# PanQHDMI.net
KiCad netlist of a schematic drawn in Altium Designer
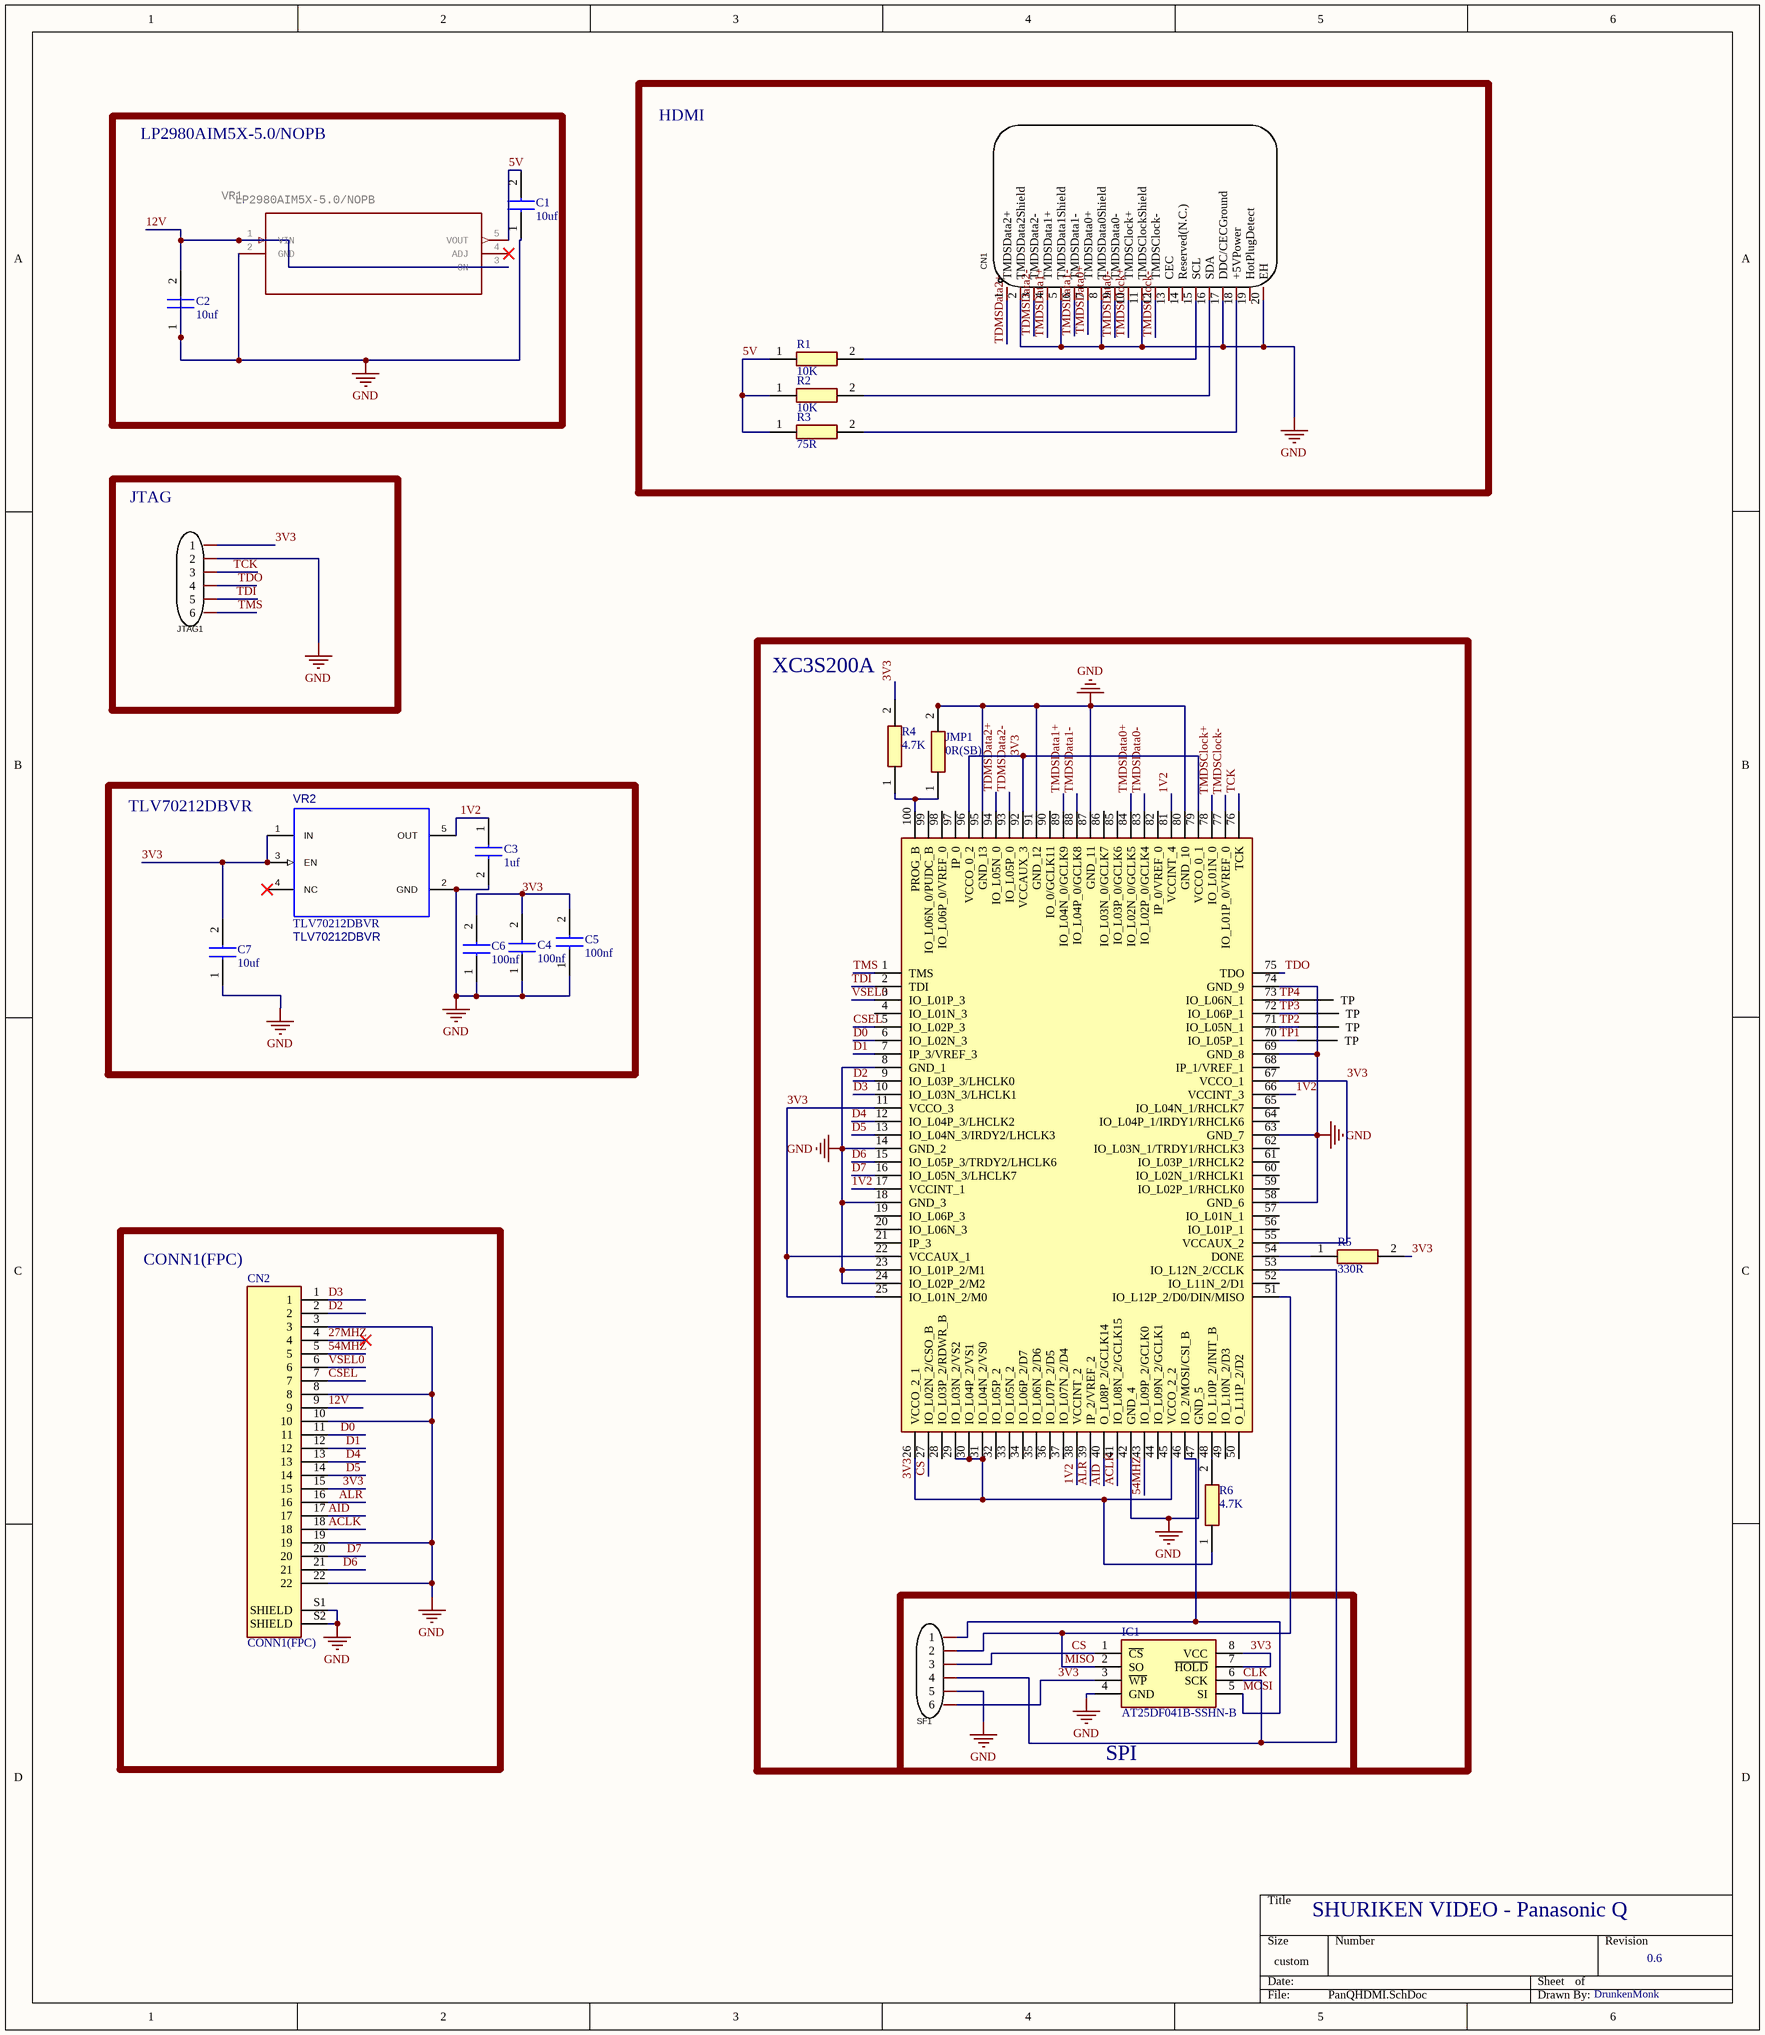
[diagram p0: PanQHDMI.SchDoc]

(export (version "E")
  (design (tool "Eeschema 10.0.6"))
  (components
    (comp (ref "C1")
      (value "10uf")
      (footprint "SamacSys:RESC2012X50N")
      (description "Capacitor")
      (fields
        (field (name "MANUFACTURER_PART_NUMBER") "08055A150JAT2A")
        (field (name "MOUSER PART NUMBER") "581-08055A150J")
      )
      (libsource (lib "*") (part "08055A150JAT2A"))
    )
    (comp (ref "C2")
      (value "10uf")
      (footprint "SamacSys:RESC2012X50N")
      (description "Capacitor")
      (fields
        (field (name "MANUFACTURER_PART_NUMBER") "08055A150JAT2A")
        (field (name "MOUSER PART NUMBER") "581-08055A150J")
      )
      (libsource (lib "*") (part "08055A150JAT2A"))
    )
    (comp (ref "C3")
      (value "1uf")
      (footprint "SamacSys:RESC2012X50N")
      (description "Capacitor")
      (fields
        (field (name "MANUFACTURER_PART_NUMBER") "08055A150JAT2A")
        (field (name "MOUSER PART NUMBER") "581-08055A150J")
      )
      (libsource (lib "*") (part "08055A150JAT2A"))
    )
    (comp (ref "C4")
      (value "100nf")
      (footprint "RESC2012X50N")
      (description "Capacitor")
      (fields
        (field (name "MANUFACTURER_PART_NUMBER") "08055A150JAT2A")
        (field (name "MOUSER PART NUMBER") "581-08055A150J")
      )
      (libsource (lib "*") (part "08055A150JAT2A"))
    )
    (comp (ref "C5")
      (value "100nf")
      (footprint "RESC2012X50N")
      (description "Capacitor")
      (fields
        (field (name "MANUFACTURER_PART_NUMBER") "08055A150JAT2A")
        (field (name "MOUSER PART NUMBER") "581-08055A150J")
      )
      (libsource (lib "*") (part "08055A150JAT2A"))
    )
    (comp (ref "C6")
      (value "100nf")
      (footprint "SamacSys:RESC2012X50N")
      (description "Capacitor")
      (fields
        (field (name "MANUFACTURER_PART_NUMBER") "08055A150JAT2A")
        (field (name "MOUSER PART NUMBER") "581-08055A150J")
      )
      (libsource (lib "*") (part "08055A150JAT2A"))
    )
    (comp (ref "C7")
      (value "10uf")
      (footprint "SamacSys:RESC2012X50N")
      (description "Capacitor")
      (fields
        (field (name "MANUFACTURER_PART_NUMBER") "08055A150JAT2A")
        (field (name "MOUSER PART NUMBER") "581-08055A150J")
      )
      (libsource (lib "*") (part "08055A150JAT2A"))
    )
    (comp (ref "CN1")
      (value "10029449-111RLF")
      (footprint "HDMI-SMD_10029449-001RLF")
      (fields (field (name "MANUFACTURER") "Amphenol"))
      (libsource (lib "altium-import") (part "root_1_10029449-111RLF_"))
    )
    (comp (ref "CN2")
      (value "CONN1(FPC)")
      (footprint "SamacSys:XF3M122151B")
      (description "Conn FPC Connector SKT 22 POS 1mm Solder RA SMD Automotive T/R")
      (fields (field (name "MP") "2-84953-2") (field (name "MF") "TE Connectivity / AMP"))
      (libsource (lib "2-84953-2") (part "2-84953-2"))
    )
    (comp (ref "IC1")
      (value "AT25DF041B-SSHN-B")
      (footprint "SamacSys:SOIC127P600X175-8N")
      (description "Integrated Circuit")
      (fields (field (name "MOUSER PART NUMBER") "988-AT25DF041BSSHNB"))
      (libsource (lib "*") (part "AT25DF041B-SSHN-B"))
    )
    (comp (ref "JMP1")
      (value "0R(SB)")
      (footprint "SamacSys:RESC2012X50N")
      (description "Resistor")
      (fields (field (name "MANUFACTURER_PART_NUMBER") "CPF0805B102RE1"))
      (libsource (lib "*") (part "CPF0805B102RE1"))
    )
    (comp (ref "JTAG1")
      (value "2.54-1x6P直针")
      (footprint "TC2030MCP")
      (fields (field (name "MANUFACTURER") "BOOMELE(博穆精密)"))
      (libsource (lib "altium-import") (part "root_0_mirrored_2.54-1x6P直针_"))
    )
    (comp (ref "R1")
      (value "10K")
      (footprint "SamacSys:RESC2012X50N")
      (description "Resistor")
      (fields (field (name "MANUFACTURER_PART_NUMBER") "CPF0805B102RE1"))
      (libsource (lib "") (part "CPF0805B102RE1_1"))
    )
    (comp (ref "R2")
      (value "10K")
      (footprint "SamacSys:RESC2012X50N")
      (description "Resistor")
      (fields (field (name "MANUFACTURER_PART_NUMBER") "CPF0805B102RE1"))
      (libsource (lib "") (part "CPF0805B102RE1_1"))
    )
    (comp (ref "R3")
      (value "75R")
      (footprint "SamacSys:RESC2012X50N")
      (description "Resistor")
      (fields (field (name "MANUFACTURER_PART_NUMBER") "CPF0805B102RE1"))
      (libsource (lib "") (part "CPF0805B102RE1_1"))
    )
    (comp (ref "R4")
      (value "4.7K")
      (footprint "SamacSys:RESC2012X50N")
      (description "Resistor")
      (fields (field (name "MANUFACTURER_PART_NUMBER") "CPF0805B102RE1"))
      (libsource (lib "*") (part "CPF0805B102RE1"))
    )
    (comp (ref "R5")
      (value "330R")
      (footprint "SamacSys:RESC2012X50N")
      (description "Resistor")
      (fields (field (name "MANUFACTURER_PART_NUMBER") "CPF0805B102RE1"))
      (libsource (lib "") (part "CPF0805B102RE1_1"))
    )
    (comp (ref "R6")
      (value "4.7K")
      (footprint "SamacSys:RESC2012X50N")
      (description "Resistor")
      (fields (field (name "MANUFACTURER_PART_NUMBER") "CPF0805B102RE1"))
      (libsource (lib "*") (part "CPF0805B102RE1"))
    )
    (comp (ref "SF1")
      (value "2.54-1x6P直针")
      (footprint "TC2030MCP")
      (fields (field (name "MANUFACTURER") "BOOMELE(博穆精密)"))
      (libsource (lib "altium-import") (part "root_0_mirrored_2.54-1x6P直针_"))
    )
    (comp (ref "TP1")
      (value "Component_1")
      (footprint "TP1")
      (libsource (lib "singlepad") (part "Component_1"))
    )
    (comp (ref "TP2")
      (value "Component_1")
      (footprint "TP1")
      (libsource (lib "singlepad") (part "Component_1"))
    )
    (comp (ref "TP3")
      (value "Component_1")
      (footprint "TP1")
      (libsource (lib "singlepad") (part "Component_1"))
    )
    (comp (ref "TP4")
      (value "Component_1")
      (footprint "TP1")
      (libsource (lib "singlepad") (part "Component_1"))
    )
    (comp (ref "U1")
      (value "~")
      (footprint "SamacSys:QFP50P1600X1600X120-100N")
      (description "Integrated Circuit")
      (fields
        (field (name "MANUFACTURER_PART_NUMBER") "XC3S200A-4VQG100C")
        (field (name "MOUSER PART NUMBER") "217-C3S200A-4VQG100C")
      )
      (libsource (lib "SamacSys") (part "XC3S200A-4VQG100C"))
    )
    (comp (ref "VR1")
      (value "LP2980AIM5X-5.0/NOPB")
      (footprint "MF05A_TEX")
      (fields (field (name "COPYRIGHT") "Copyright (C) 2024 Ultra Librarian. All rights reserved."))
      (libsource (lib "5Vout.Library") (part "LP2980AIM5X-5.0/NOPB"))
    )
    (comp (ref "VR2")
      (value "TLV70212DBVR")
      (footprint "MF05A_TEX")
      (fields (field (name "ALTIUM_VALUE") "TLV70212DBVR"))
      (libsource (lib "2024-10-28_18-48-43") (part "TLV70212DBVR"))
    )
  )
  (nets
    (net (code "1") (name "/1V2") (class "Default")
      (node (ref "C3") (pin "1") (pinfunction "1_1") (pintype "passive"))
      (node (ref "U1") (pin "17") (pinfunction "VCCINT_1_17") (pintype "passive"))
      (node (ref "U1") (pin "38") (pinfunction "VCCINT_2_38") (pintype "passive"))
      (node (ref "U1") (pin "66") (pinfunction "VCCINT_3_66") (pintype "passive"))
      (node (ref "U1") (pin "81") (pinfunction "VCCINT_4_81") (pintype "passive"))
      (node (ref "VR2") (pin "5") (pinfunction "OUT_5") (pintype "power_in"))
    )
    (net (code "2") (name "/3V3") (class "Default")
      (node (ref "C4") (pin "2") (pinfunction "2_2") (pintype "passive"))
      (node (ref "C5") (pin "2") (pinfunction "2_2") (pintype "passive"))
      (node (ref "C6") (pin "2") (pinfunction "2_2") (pintype "passive"))
      (node (ref "C7") (pin "2") (pinfunction "2_2") (pintype "passive"))
      (node (ref "CN2") (pin "15") (pinfunction "15_15") (pintype "passive"))
      (node (ref "IC1") (pin "3") (pinfunction "~{WP}_3") (pintype "passive"))
      (node (ref "IC1") (pin "7") (pinfunction "~{HOLD}_7") (pintype "passive"))
      (node (ref "IC1") (pin "8") (pinfunction "VCC_8") (pintype "passive"))
      (node (ref "JTAG1") (pin "1") (pinfunction "1_1") (pintype "passive"))
      (node (ref "R4") (pin "2") (pinfunction "2_2") (pintype "passive"))
      (node (ref "R5") (pin "2") (pinfunction "2_2") (pintype "passive"))
      (node (ref "R6") (pin "1") (pinfunction "1_1") (pintype "passive"))
      (node (ref "SF1") (pin "6") (pinfunction "6_6") (pintype "passive"))
      (node (ref "U1") (pin "11") (pinfunction "VCCO_3_11") (pintype "passive"))
      (node (ref "U1") (pin "22") (pinfunction "VCCAUX_1_22") (pintype "passive"))
      (node (ref "U1") (pin "25") (pinfunction "IO_L01N_2/M0_25") (pintype "passive"))
      (node (ref "U1") (pin "26") (pinfunction "VCCO_2_1_26") (pintype "passive"))
      (node (ref "U1") (pin "29") (pinfunction "IO_L03N_2/VS2_29") (pintype "passive"))
      (node (ref "U1") (pin "30") (pinfunction "IO_L04P_2/VS1_30") (pintype "passive"))
      (node (ref "U1") (pin "31") (pinfunction "IO_L04N_2/VS0_31") (pintype "passive"))
      (node (ref "U1") (pin "45") (pinfunction "VCCO_2_2_45") (pintype "passive"))
      (node (ref "U1") (pin "55") (pinfunction "VCCAUX_2_55") (pintype "passive"))
      (node (ref "U1") (pin "67") (pinfunction "VCCO_1_67") (pintype "passive"))
      (node (ref "U1") (pin "79") (pinfunction "VCCO_0_1_79") (pintype "passive"))
      (node (ref "U1") (pin "92") (pinfunction "VCCAUX_3_92") (pintype "passive"))
      (node (ref "U1") (pin "96") (pinfunction "VCCO_0_2_96") (pintype "passive"))
      (node (ref "VR2") (pin "1") (pinfunction "IN_1") (pintype "power_in"))
      (node (ref "VR2") (pin "3") (pinfunction "EN_3") (pintype "input"))
    )
    (net (code "3") (name "/5V") (class "Default")
      (node (ref "C1") (pin "2") (pinfunction "2_2") (pintype "passive"))
      (node (ref "R1") (pin "1") (pinfunction "1_1") (pintype "passive"))
      (node (ref "R2") (pin "1") (pinfunction "1_1") (pintype "passive"))
      (node (ref "R3") (pin "1") (pinfunction "1_1") (pintype "passive"))
      (node (ref "VR1") (pin "5") (pinfunction "VOUT_5") (pintype "output"))
    )
    (net (code "4") (name "/12V") (class "Default")
      (node (ref "C2") (pin "2") (pinfunction "2_2") (pintype "passive"))
      (node (ref "CN2") (pin "9") (pinfunction "9_9") (pintype "power_in"))
      (node (ref "VR1") (pin "1") (pinfunction "VIN_1") (pintype "input"))
      (node (ref "VR1") (pin "3") (pinfunction "ON_3") (pintype "passive"))
    )
    (net (code "5") (name "/27MHZ") (class "Default")
      (node (ref "CN2") (pin "4") (pinfunction "4_4") (pintype "passive+no_connect"))
    )
    (net (code "6") (name "/54MHZ") (class "Default")
      (node (ref "CN2") (pin "5") (pinfunction "5_5") (pintype "passive"))
      (node (ref "U1") (pin "43") (pinfunction "IO_L09P_2/GCLK0_43") (pintype "passive"))
    )
    (net (code "7") (name "/ACLK") (class "Default")
      (node (ref "CN2") (pin "18") (pinfunction "18_18") (pintype "passive"))
      (node (ref "U1") (pin "41") (pinfunction "IO_L08N_2/GCLK15_41") (pintype "passive"))
    )
    (net (code "8") (name "/AID") (class "Default")
      (node (ref "CN2") (pin "17") (pinfunction "17_17") (pintype "passive"))
      (node (ref "U1") (pin "40") (pinfunction "O_L08P_2/GCLK14_40") (pintype "passive"))
    )
    (net (code "9") (name "/ALR") (class "Default")
      (node (ref "CN2") (pin "16") (pinfunction "16_16") (pintype "passive"))
      (node (ref "U1") (pin "39") (pinfunction "IP_2/VREF_2_39") (pintype "passive"))
    )
    (net (code "10") (name "/CLK") (class "Default")
      (node (ref "IC1") (pin "6") (pinfunction "SCK_6") (pintype "passive"))
      (node (ref "SF1") (pin "4") (pinfunction "4_4") (pintype "passive"))
      (node (ref "U1") (pin "53") (pinfunction "IO_L12N_2/CCLK_53") (pintype "passive"))
    )
    (net (code "11") (name "/CS") (class "Default")
      (node (ref "IC1") (pin "1") (pinfunction "~{CS}_1") (pintype "passive"))
      (node (ref "SF1") (pin "3") (pinfunction "3_3") (pintype "passive"))
      (node (ref "U1") (pin "27") (pinfunction "IO_L02N_2/CSO_B_27") (pintype "passive"))
    )
    (net (code "12") (name "/CSEL") (class "Default")
      (node (ref "CN2") (pin "7") (pinfunction "7_7") (pintype "passive"))
      (node (ref "U1") (pin "5") (pinfunction "IO_L02P_3_5") (pintype "passive"))
    )
    (net (code "13") (name "/D0") (class "Default")
      (node (ref "CN2") (pin "11") (pinfunction "11_11") (pintype "passive"))
      (node (ref "U1") (pin "6") (pinfunction "IO_L02N_3_6") (pintype "passive"))
    )
    (net (code "14") (name "/D1") (class "Default")
      (node (ref "CN2") (pin "12") (pinfunction "12_12") (pintype "passive"))
      (node (ref "U1") (pin "7") (pinfunction "IP_3/VREF_3_7") (pintype "passive"))
    )
    (net (code "15") (name "/D2") (class "Default")
      (node (ref "CN2") (pin "2") (pinfunction "2_2") (pintype "passive"))
      (node (ref "U1") (pin "9") (pinfunction "IO_L03P_3/LHCLK0_9") (pintype "passive"))
    )
    (net (code "16") (name "/D3") (class "Default")
      (node (ref "CN2") (pin "1") (pinfunction "1_1") (pintype "passive"))
      (node (ref "U1") (pin "10") (pinfunction "IO_L03N_3/LHCLK1_10") (pintype "passive"))
    )
    (net (code "17") (name "/D4") (class "Default")
      (node (ref "CN2") (pin "13") (pinfunction "13_13") (pintype "passive"))
      (node (ref "U1") (pin "12") (pinfunction "IO_L04P_3/LHCLK2_12") (pintype "passive"))
    )
    (net (code "18") (name "/D5") (class "Default")
      (node (ref "CN2") (pin "14") (pinfunction "14_14") (pintype "passive"))
      (node (ref "U1") (pin "13") (pinfunction "IO_L04N_3/IRDY2/LHCLK3_13") (pintype "passive"))
    )
    (net (code "19") (name "/D6") (class "Default")
      (node (ref "CN2") (pin "21") (pinfunction "21_21") (pintype "passive"))
      (node (ref "U1") (pin "15") (pinfunction "IO_L05P_3/TRDY2/LHCLK6_15") (pintype "passive"))
    )
    (net (code "20") (name "/D7") (class "Default")
      (node (ref "CN2") (pin "20") (pinfunction "20_20") (pintype "passive"))
      (node (ref "U1") (pin "16") (pinfunction "IO_L05N_3/LHCLK7_16") (pintype "passive"))
    )
    (net (code "21") (name "/MISO") (class "Default")
      (node (ref "IC1") (pin "2") (pinfunction "SO_2") (pintype "passive"))
      (node (ref "SF1") (pin "2") (pinfunction "2_2") (pintype "passive"))
      (node (ref "U1") (pin "51") (pinfunction "IO_L12P_2/D0/DIN/MISO_51") (pintype "passive"))
    )
    (net (code "22") (name "/MOSI") (class "Default")
      (node (ref "IC1") (pin "5") (pinfunction "SI_5") (pintype "passive"))
      (node (ref "SF1") (pin "1") (pinfunction "1_1") (pintype "passive"))
      (node (ref "U1") (pin "46") (pinfunction "IO_2/MOSI/CSI_B_46") (pintype "passive"))
    )
    (net (code "23") (name "/TCK") (class "Default")
      (node (ref "JTAG1") (pin "3") (pinfunction "3_3") (pintype "passive"))
      (node (ref "U1") (pin "76") (pinfunction "TCK_76") (pintype "passive"))
    )
    (net (code "24") (name "/TDI") (class "Default")
      (node (ref "JTAG1") (pin "5") (pinfunction "5_5") (pintype "passive"))
      (node (ref "U1") (pin "2") (pinfunction "TDI_2") (pintype "passive"))
    )
    (net (code "25") (name "/TDMSData2+") (class "Default")
      (node (ref "CN1") (pin "1") (pinfunction "TMDSData2+_1") (pintype "passive"))
      (node (ref "U1") (pin "94") (pinfunction "IO_L05N_0_94") (pintype "passive"))
    )
    (net (code "26") (name "/TDMSData2-") (class "Default")
      (node (ref "CN1") (pin "3") (pinfunction "TMDSData2-_3") (pintype "passive"))
      (node (ref "U1") (pin "93") (pinfunction "IO_L05P_0_93") (pintype "passive"))
    )
    (net (code "27") (name "/TDO") (class "Default")
      (node (ref "JTAG1") (pin "4") (pinfunction "4_4") (pintype "passive"))
      (node (ref "U1") (pin "75") (pinfunction "TDO_75") (pintype "passive"))
    )
    (net (code "28") (name "/TMDSClock+") (class "Default")
      (node (ref "CN1") (pin "10") (pinfunction "TMDSClock+_10") (pintype "passive"))
      (node (ref "U1") (pin "78") (pinfunction "IO_L01N_0_78") (pintype "passive"))
    )
    (net (code "29") (name "/TMDSClock-") (class "Default")
      (node (ref "CN1") (pin "12") (pinfunction "TMDSClock-_12") (pintype "passive"))
      (node (ref "U1") (pin "77") (pinfunction "IO_L01P_0/VREF_0_77") (pintype "passive"))
    )
    (net (code "30") (name "/TMDSData0+") (class "Default")
      (node (ref "CN1") (pin "7") (pinfunction "TMDSData0+_7") (pintype "passive"))
      (node (ref "U1") (pin "84") (pinfunction "IO_L02N_0/GCLK5_84") (pintype "passive"))
    )
    (net (code "31") (name "/TMDSData0-") (class "Default")
      (node (ref "CN1") (pin "9") (pinfunction "TMDSData0-_9") (pintype "passive"))
      (node (ref "U1") (pin "83") (pinfunction "IO_L02P_0/GCLK4_83") (pintype "passive"))
    )
    (net (code "32") (name "/TMDSData1+") (class "Default")
      (node (ref "CN1") (pin "4") (pinfunction "TMDSData1+_4") (pintype "passive"))
      (node (ref "U1") (pin "89") (pinfunction "IO_L04N_0/GCLK9_89") (pintype "passive"))
    )
    (net (code "33") (name "/TMDSData1-") (class "Default")
      (node (ref "CN1") (pin "6") (pinfunction "TMDSData1-_6") (pintype "passive"))
      (node (ref "U1") (pin "88") (pinfunction "IO_L04P_0/GCLK8_88") (pintype "passive"))
    )
    (net (code "34") (name "/TMS") (class "Default")
      (node (ref "JTAG1") (pin "6") (pinfunction "6_6") (pintype "passive"))
      (node (ref "U1") (pin "1") (pinfunction "TMS_1") (pintype "passive"))
    )
    (net (code "35") (name "/TP1") (class "Default")
      (node (ref "TP1") (pin "TP") (pinfunction "TP_TP") (pintype "passive"))
      (node (ref "U1") (pin "70") (pinfunction "IO_L05P_1_70") (pintype "passive"))
    )
    (net (code "36") (name "/TP2") (class "Default")
      (node (ref "TP2") (pin "TP") (pinfunction "TP_TP") (pintype "passive"))
      (node (ref "U1") (pin "71") (pinfunction "IO_L05N_1_71") (pintype "passive"))
    )
    (net (code "37") (name "/TP3") (class "Default")
      (node (ref "TP3") (pin "TP") (pinfunction "TP_TP") (pintype "passive"))
      (node (ref "U1") (pin "72") (pinfunction "IO_L06P_1_72") (pintype "passive"))
    )
    (net (code "38") (name "/TP4") (class "Default")
      (node (ref "TP4") (pin "TP") (pinfunction "TP_TP") (pintype "passive"))
      (node (ref "U1") (pin "73") (pinfunction "IO_L06N_1_73") (pintype "passive"))
    )
    (net (code "39") (name "/VSEL0") (class "Default")
      (node (ref "CN2") (pin "6") (pinfunction "6_6") (pintype "passive"))
      (node (ref "U1") (pin "3") (pinfunction "IO_L01P_3_3") (pintype "passive"))
    )
    (net (code "40") (name "GND") (class "Default")
      (node (ref "C1") (pin "1") (pinfunction "1_1") (pintype "passive"))
      (node (ref "C2") (pin "1") (pinfunction "1_1") (pintype "passive"))
      (node (ref "C3") (pin "2") (pinfunction "2_2") (pintype "passive"))
      (node (ref "C4") (pin "1") (pinfunction "1_1") (pintype "passive"))
      (node (ref "C5") (pin "1") (pinfunction "1_1") (pintype "passive"))
      (node (ref "C6") (pin "1") (pinfunction "1_1") (pintype "passive"))
      (node (ref "C7") (pin "1") (pinfunction "1_1") (pintype "passive"))
      (node (ref "CN1") (pin "11") (pinfunction "TMDSClockShield_11") (pintype "passive"))
      (node (ref "CN1") (pin "17") (pinfunction "DDC/CECGround_17") (pintype "passive"))
      (node (ref "CN1") (pin "2") (pinfunction "TMDSData2Shield_2") (pintype "passive"))
      (node (ref "CN1") (pin "20") (pinfunction "EH_20") (pintype "passive"))
      (node (ref "CN1") (pin "5") (pinfunction "TMDSData1Shield_5") (pintype "passive"))
      (node (ref "CN1") (pin "8") (pinfunction "TMDSData0Shield_8") (pintype "passive"))
      (node (ref "CN2") (pin "10") (pinfunction "10_10") (pintype "passive"))
      (node (ref "CN2") (pin "19") (pinfunction "19_19") (pintype "passive"))
      (node (ref "CN2") (pin "22") (pinfunction "22_22") (pintype "passive"))
      (node (ref "CN2") (pin "3") (pinfunction "3_3") (pintype "passive"))
      (node (ref "CN2") (pin "8") (pinfunction "8_8") (pintype "passive"))
      (node (ref "CN2") (pin "S1") (pinfunction "SHIELD_S1") (pintype "passive"))
      (node (ref "CN2") (pin "S2") (pinfunction "SHIELD_S2") (pintype "passive"))
      (node (ref "IC1") (pin "4") (pinfunction "GND_4") (pintype "passive"))
      (node (ref "JMP1") (pin "2") (pinfunction "2_2") (pintype "passive"))
      (node (ref "JTAG1") (pin "2") (pinfunction "2_2") (pintype "passive"))
      (node (ref "SF1") (pin "5") (pinfunction "5_5") (pintype "passive"))
      (node (ref "U1") (pin "14") (pinfunction "GND_2_14") (pintype "passive"))
      (node (ref "U1") (pin "18") (pinfunction "GND_3_18") (pintype "passive"))
      (node (ref "U1") (pin "23") (pinfunction "IO_L01P_2/M1_23") (pintype "passive"))
      (node (ref "U1") (pin "24") (pinfunction "IO_L02P_2/M2_24") (pintype "passive"))
      (node (ref "U1") (pin "42") (pinfunction "GND_4_42") (pintype "passive"))
      (node (ref "U1") (pin "47") (pinfunction "GND_5_47") (pintype "passive"))
      (node (ref "U1") (pin "58") (pinfunction "GND_6_58") (pintype "passive"))
      (node (ref "U1") (pin "63") (pinfunction "GND_7_63") (pintype "passive"))
      (node (ref "U1") (pin "69") (pinfunction "GND_8_69") (pintype "passive"))
      (node (ref "U1") (pin "74") (pinfunction "GND_9_74") (pintype "passive"))
      (node (ref "U1") (pin "8") (pinfunction "GND_1_8") (pintype "passive"))
      (node (ref "U1") (pin "80") (pinfunction "GND_10_80") (pintype "passive"))
      (node (ref "U1") (pin "87") (pinfunction "GND_11_87") (pintype "passive"))
      (node (ref "U1") (pin "91") (pinfunction "GND_12_91") (pintype "passive"))
      (node (ref "U1") (pin "95") (pinfunction "GND_13_95") (pintype "passive"))
      (node (ref "VR1") (pin "2") (pinfunction "GND_2") (pintype "passive"))
      (node (ref "VR2") (pin "2") (pinfunction "GND_2") (pintype "power_in"))
    )
    (net (code "41") (name "Net-(CN1-+5VPower)") (class "Default")
      (node (ref "CN1") (pin "18") (pinfunction "+5VPower_18") (pintype "passive"))
      (node (ref "R3") (pin "2") (pinfunction "2_2") (pintype "passive"))
    )
    (net (code "42") (name "Net-(CN1-SCL)") (class "Default")
      (node (ref "CN1") (pin "15") (pinfunction "SCL_15") (pintype "passive"))
      (node (ref "R1") (pin "2") (pinfunction "2_2") (pintype "passive"))
    )
    (net (code "43") (name "Net-(CN1-SDA)") (class "Default")
      (node (ref "CN1") (pin "16") (pinfunction "SDA_16") (pintype "passive"))
      (node (ref "R2") (pin "2") (pinfunction "2_2") (pintype "passive"))
    )
    (net (code "44") (name "Net-(U1-DONE)") (class "Default")
      (node (ref "R5") (pin "1") (pinfunction "1_1") (pintype "passive"))
      (node (ref "U1") (pin "54") (pinfunction "DONE_54") (pintype "passive"))
    )
    (net (code "45") (name "Net-(U1-IO_L10P_2{slash}INIT_B)") (class "Default")
      (node (ref "R6") (pin "2") (pinfunction "2_2") (pintype "passive"))
      (node (ref "U1") (pin "48") (pinfunction "IO_L10P_2/INIT_B_48") (pintype "passive"))
    )
    (net (code "46") (name "Net-(U1-PROG_B)") (class "Default")
      (node (ref "JMP1") (pin "1") (pinfunction "1_1") (pintype "passive"))
      (node (ref "R4") (pin "1") (pinfunction "1_1") (pintype "passive"))
      (node (ref "U1") (pin "100") (pinfunction "PROG_B_100") (pintype "passive"))
    )
    (net (code "47") (name "unconnected-(CN1-CEC-Pad13)") (class "Default")
      (node (ref "CN1") (pin "13") (pinfunction "CEC_13") (pintype "passive"))
    )
    (net (code "48") (name "unconnected-(CN1-HotPlugDetect-Pad19)") (class "Default")
      (node (ref "CN1") (pin "19") (pinfunction "HotPlugDetect_19") (pintype "passive"))
    )
    (net (code "49") (name "unconnected-(CN1-Reserved(N.C.)-Pad14)") (class "Default")
      (node (ref "CN1") (pin "14") (pinfunction "Reserved(N.C.)_14") (pintype "passive"))
    )
    (net (code "50") (name "unconnected-(U1-IO_0{slash}GCLK11-Pad90)") (class "Default")
      (node (ref "U1") (pin "90") (pinfunction "IO_0/GCLK11_90") (pintype "passive"))
    )
    (net (code "51") (name "unconnected-(U1-IO_L01N_1-Pad57)") (class "Default")
      (node (ref "U1") (pin "57") (pinfunction "IO_L01N_1_57") (pintype "passive"))
    )
    (net (code "52") (name "unconnected-(U1-IO_L01N_3-Pad4)") (class "Default")
      (node (ref "U1") (pin "4") (pinfunction "IO_L01N_3_4") (pintype "passive"))
    )
    (net (code "53") (name "unconnected-(U1-IO_L01P_1-Pad56)") (class "Default")
      (node (ref "U1") (pin "56") (pinfunction "IO_L01P_1_56") (pintype "passive"))
    )
    (net (code "54") (name "unconnected-(U1-IO_L02N_1{slash}RHCLK1-Pad60)") (class "Default")
      (node (ref "U1") (pin "60") (pinfunction "IO_L02N_1/RHCLK1_60") (pintype "passive"))
    )
    (net (code "55") (name "unconnected-(U1-IO_L02P_1{slash}RHCLK0-Pad59)") (class "Default")
      (node (ref "U1") (pin "59") (pinfunction "IO_L02P_1/RHCLK0_59") (pintype "passive"))
    )
    (net (code "56") (name "unconnected-(U1-IO_L03N_0{slash}GCLK7-Pad86)") (class "Default")
      (node (ref "U1") (pin "86") (pinfunction "IO_L03N_0/GCLK7_86") (pintype "passive"))
    )
    (net (code "57") (name "unconnected-(U1-IO_L03N_1{slash}TRDY1{slash}RHCLK3-Pad62)") (class "Default")
      (node (ref "U1") (pin "62") (pinfunction "IO_L03N_1/TRDY1/RHCLK3_62") (pintype "passive"))
    )
    (net (code "58") (name "unconnected-(U1-IO_L03P_0{slash}GCLK6-Pad85)") (class "Default")
      (node (ref "U1") (pin "85") (pinfunction "IO_L03P_0/GCLK6_85") (pintype "passive"))
    )
    (net (code "59") (name "unconnected-(U1-IO_L03P_1{slash}RHCLK2-Pad61)") (class "Default")
      (node (ref "U1") (pin "61") (pinfunction "IO_L03P_1/RHCLK2_61") (pintype "passive"))
    )
    (net (code "60") (name "unconnected-(U1-IO_L03P_2{slash}RDWR_B-Pad28)") (class "Default")
      (node (ref "U1") (pin "28") (pinfunction "IO_L03P_2/RDWR_B_28") (pintype "passive"))
    )
    (net (code "61") (name "unconnected-(U1-IO_L04N_1{slash}RHCLK7-Pad65)") (class "Default")
      (node (ref "U1") (pin "65") (pinfunction "IO_L04N_1/RHCLK7_65") (pintype "passive"))
    )
    (net (code "62") (name "unconnected-(U1-IO_L04P_1{slash}IRDY1{slash}RHCLK6-Pad64)") (class "Default")
      (node (ref "U1") (pin "64") (pinfunction "IO_L04P_1/IRDY1/RHCLK6_64") (pintype "passive"))
    )
    (net (code "63") (name "unconnected-(U1-IO_L05N_2-Pad33)") (class "Default")
      (node (ref "U1") (pin "33") (pinfunction "IO_L05N_2_33") (pintype "passive"))
    )
    (net (code "64") (name "unconnected-(U1-IO_L05P_2-Pad32)") (class "Default")
      (node (ref "U1") (pin "32") (pinfunction "IO_L05P_2_32") (pintype "passive"))
    )
    (net (code "65") (name "unconnected-(U1-IO_L06N_0{slash}PUDC_B-Pad99)") (class "Default")
      (node (ref "U1") (pin "99") (pinfunction "IO_L06N_0/PUDC_B_99") (pintype "passive"))
    )
    (net (code "66") (name "unconnected-(U1-IO_L06N_2{slash}D6-Pad35)") (class "Default")
      (node (ref "U1") (pin "35") (pinfunction "IO_L06N_2/D6_35") (pintype "passive"))
    )
    (net (code "67") (name "unconnected-(U1-IO_L06N_3-Pad20)") (class "Default")
      (node (ref "U1") (pin "20") (pinfunction "IO_L06N_3_20") (pintype "passive"))
    )
    (net (code "68") (name "unconnected-(U1-IO_L06P_0{slash}VREF_0-Pad98)") (class "Default")
      (node (ref "U1") (pin "98") (pinfunction "IO_L06P_0/VREF_0_98") (pintype "passive"))
    )
    (net (code "69") (name "unconnected-(U1-IO_L06P_2{slash}D7-Pad34)") (class "Default")
      (node (ref "U1") (pin "34") (pinfunction "IO_L06P_2/D7_34") (pintype "passive"))
    )
    (net (code "70") (name "unconnected-(U1-IO_L06P_3-Pad19)") (class "Default")
      (node (ref "U1") (pin "19") (pinfunction "IO_L06P_3_19") (pintype "passive"))
    )
    (net (code "71") (name "unconnected-(U1-IO_L07N_2{slash}D4-Pad37)") (class "Default")
      (node (ref "U1") (pin "37") (pinfunction "IO_L07N_2/D4_37") (pintype "passive"))
    )
    (net (code "72") (name "unconnected-(U1-IO_L07P_2{slash}D5-Pad36)") (class "Default")
      (node (ref "U1") (pin "36") (pinfunction "IO_L07P_2/D5_36") (pintype "passive"))
    )
    (net (code "73") (name "unconnected-(U1-IO_L09N_2{slash}GCLK1-Pad44)") (class "Default")
      (node (ref "U1") (pin "44") (pinfunction "IO_L09N_2/GCLK1_44") (pintype "passive"))
    )
    (net (code "74") (name "unconnected-(U1-IO_L10N_2{slash}D3-Pad49)") (class "Default")
      (node (ref "U1") (pin "49") (pinfunction "IO_L10N_2/D3_49") (pintype "passive"))
    )
    (net (code "75") (name "unconnected-(U1-IO_L11N_2{slash}D1-Pad52)") (class "Default")
      (node (ref "U1") (pin "52") (pinfunction "IO_L11N_2/D1_52") (pintype "passive"))
    )
    (net (code "76") (name "unconnected-(U1-IP_0-Pad97)") (class "Default")
      (node (ref "U1") (pin "97") (pinfunction "IP_0_97") (pintype "passive"))
    )
    (net (code "77") (name "unconnected-(U1-IP_0{slash}VREF_0-Pad82)") (class "Default")
      (node (ref "U1") (pin "82") (pinfunction "IP_0/VREF_0_82") (pintype "passive"))
    )
    (net (code "78") (name "unconnected-(U1-IP_1{slash}VREF_1-Pad68)") (class "Default")
      (node (ref "U1") (pin "68") (pinfunction "IP_1/VREF_1_68") (pintype "passive"))
    )
    (net (code "79") (name "unconnected-(U1-IP_3-Pad21)") (class "Default")
      (node (ref "U1") (pin "21") (pinfunction "IP_3_21") (pintype "passive"))
    )
    (net (code "80") (name "unconnected-(U1-O_L11P_2{slash}D2-Pad50)") (class "Default")
      (node (ref "U1") (pin "50") (pinfunction "O_L11P_2/D2_50") (pintype "passive"))
    )
    (net (code "81") (name "unconnected-(VR1-ADJ-Pad4)") (class "Default")
      (node (ref "VR1") (pin "4") (pinfunction "ADJ_4") (pintype "passive+no_connect"))
    )
    (net (code "82") (name "unconnected-(VR2-NC-Pad4)") (class "Default")
      (node (ref "VR2") (pin "4") (pinfunction "NC_4") (pintype "passive+no_connect"))
    )
  )
)
